# ProProject_AmaizeTrack.net
KiCad netlist of a schematic drawn in EasyEDA Pro
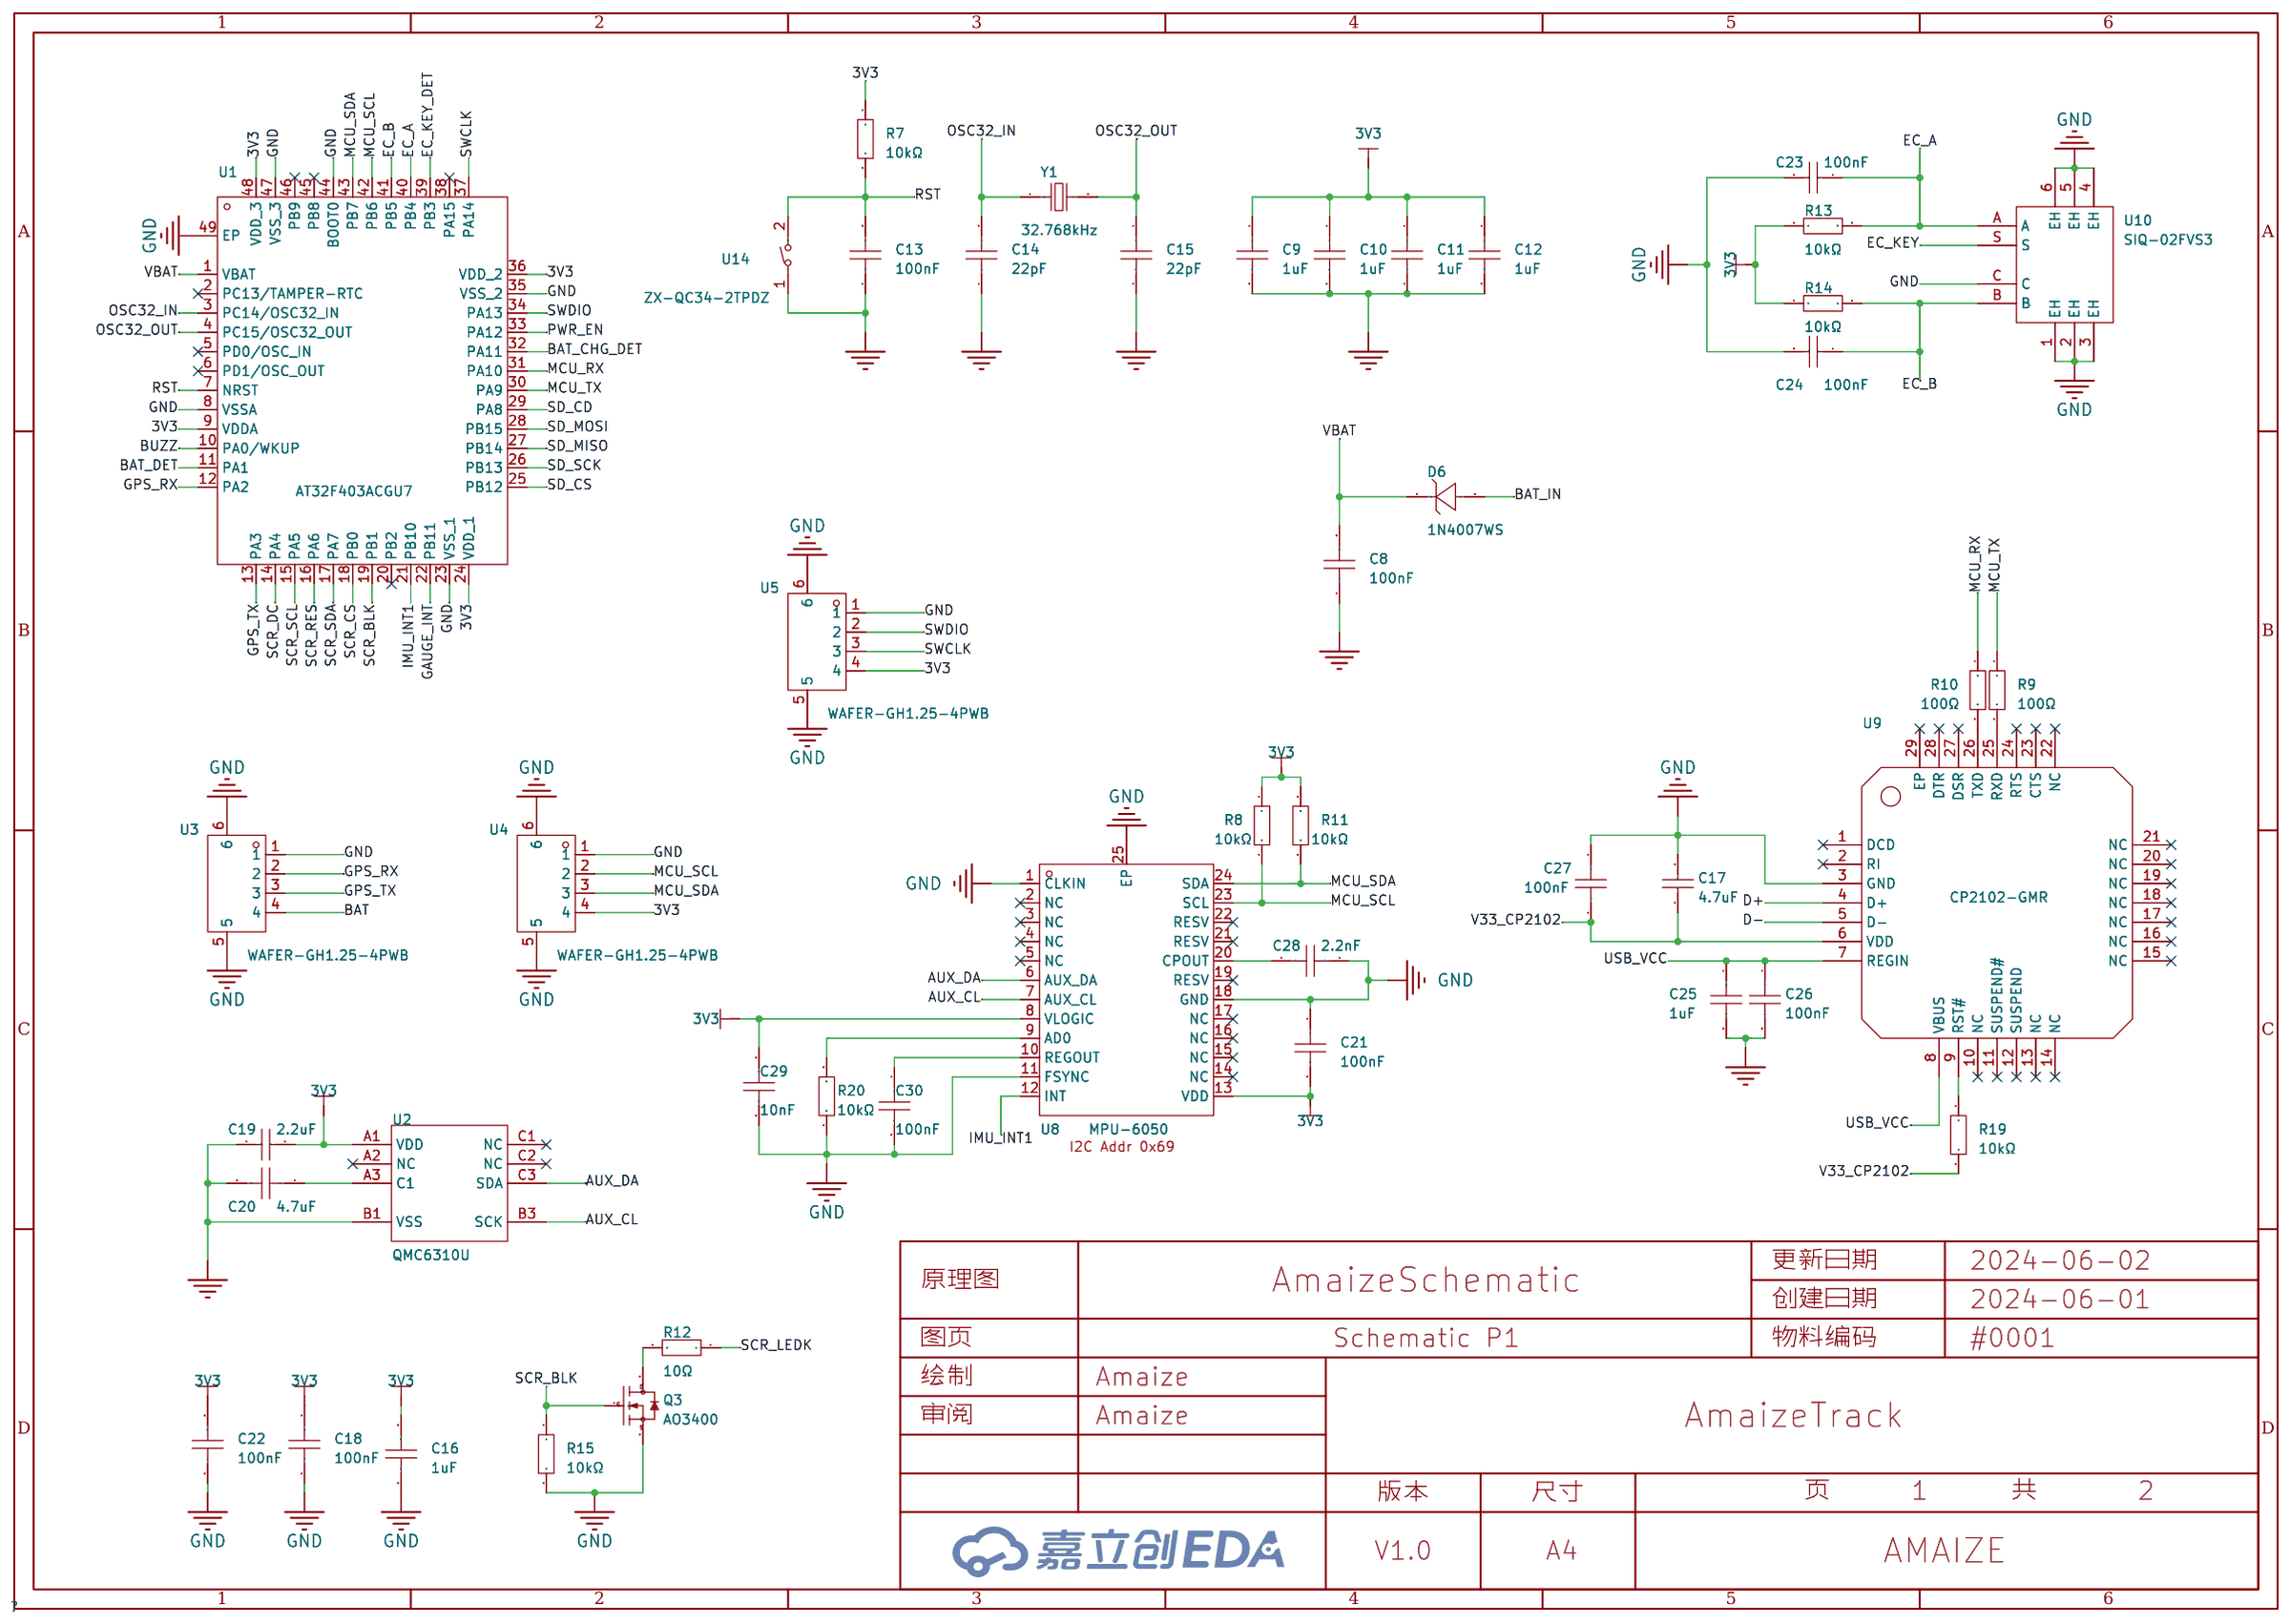
[diagram p0: Schematic P1]
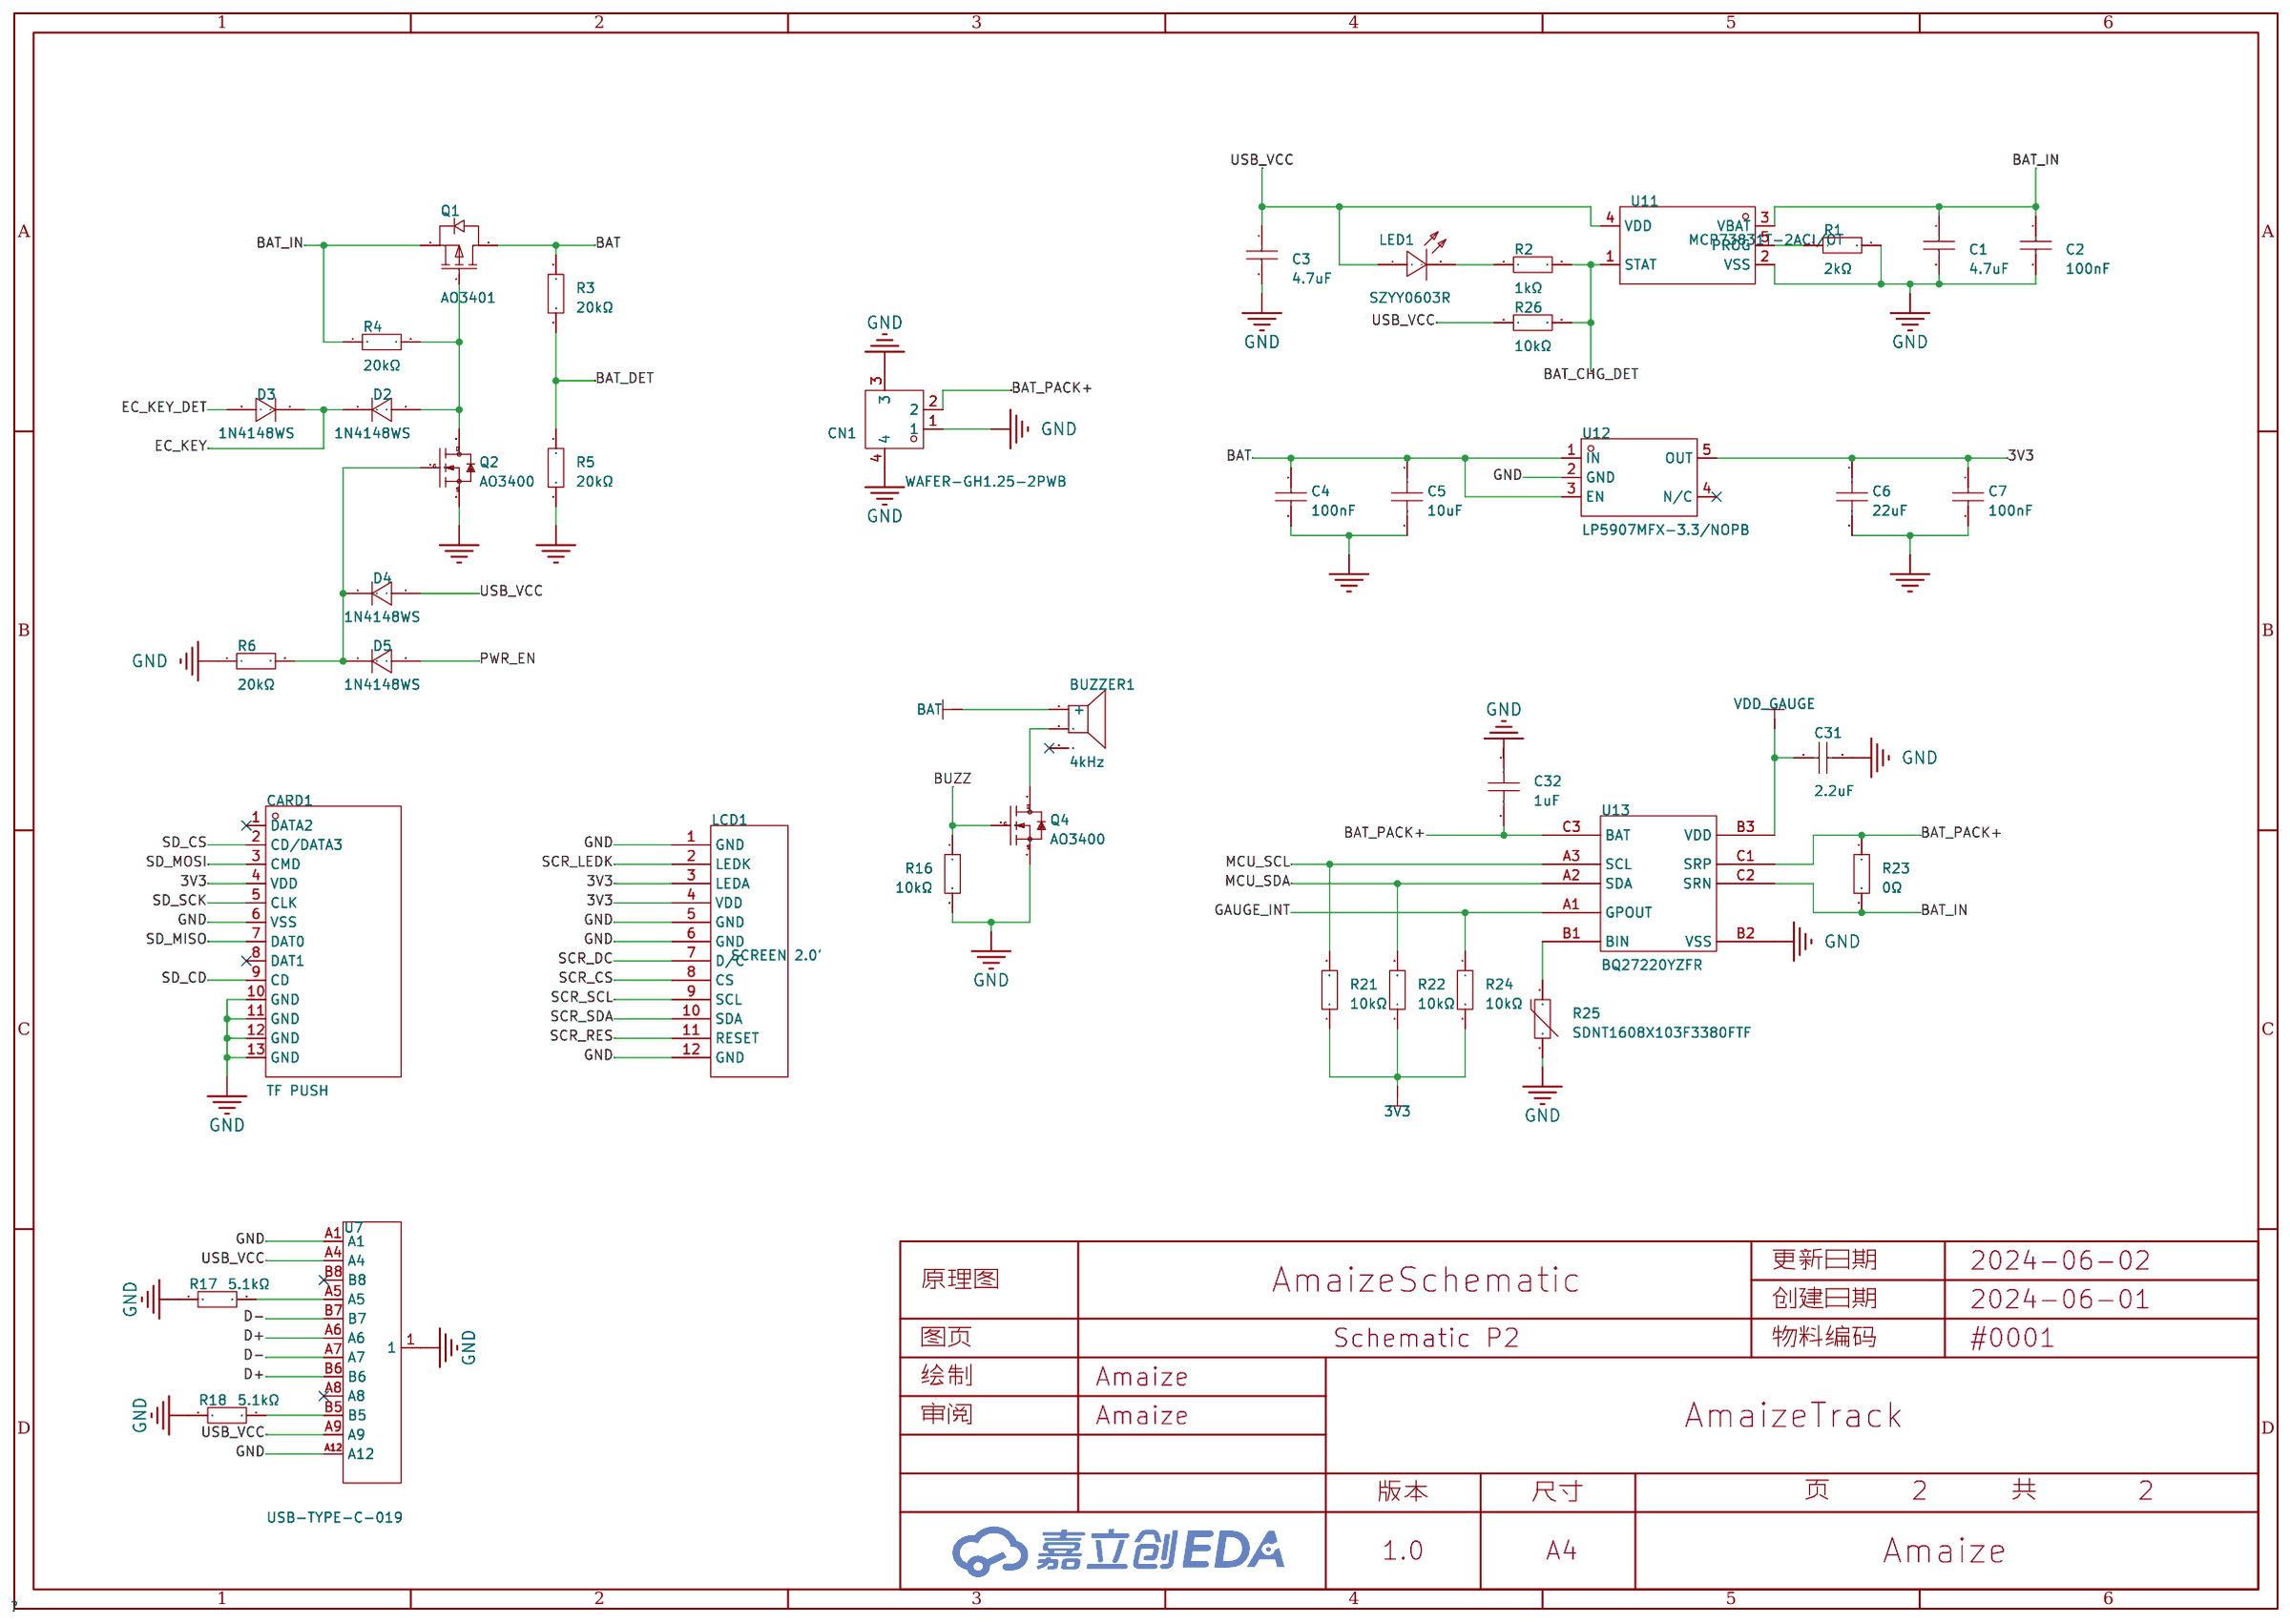
[diagram p1: Schematic P2]

(export (version "E")
  (design (tool "Eeschema 10.0.6"))
  (components
    (comp (ref "C8")
      (value "100nF")
      (footprint "easyedapro:C0603")
      (fields
        (field (name "Manufacturer Part") "CC0603KRX7R9BB104")
        (field (name "Manufacturer") "YAGEO(国巨)")
      )
      (libsource (lib "easyedapro") (part "CapAcitance"))
    )
    (comp (ref "C9")
      (value "1uF")
      (footprint "easyedapro:C0603")
      (fields
        (field (name "Manufacturer Part") "CL10A105KB8NNNC")
        (field (name "Manufacturer") "SAMSUNG(三星)")
      )
      (libsource (lib "easyedapro") (part "CapAcitance"))
    )
    (comp (ref "C10")
      (value "1uF")
      (footprint "easyedapro:C0603")
      (fields
        (field (name "Manufacturer Part") "CL10A105KB8NNNC")
        (field (name "Manufacturer") "SAMSUNG(三星)")
      )
      (libsource (lib "easyedapro") (part "CapAcitance"))
    )
    (comp (ref "C11")
      (value "1uF")
      (footprint "easyedapro:C0603")
      (fields
        (field (name "Manufacturer Part") "CL10A105KB8NNNC")
        (field (name "Manufacturer") "SAMSUNG(三星)")
      )
      (libsource (lib "easyedapro") (part "CapAcitance"))
    )
    (comp (ref "C12")
      (value "1uF")
      (footprint "easyedapro:C0603")
      (fields
        (field (name "Manufacturer Part") "CL10A105KB8NNNC")
        (field (name "Manufacturer") "SAMSUNG(三星)")
      )
      (libsource (lib "easyedapro") (part "CapAcitance"))
    )
    (comp (ref "C13")
      (value "100nF")
      (footprint "easyedapro:C0603")
      (fields
        (field (name "Manufacturer Part") "CC0603KRX7R9BB104")
        (field (name "Manufacturer") "YAGEO(国巨)")
      )
      (libsource (lib "easyedapro") (part "CapAcitance"))
    )
    (comp (ref "C14")
      (value "22pF")
      (footprint "easyedapro:C0603")
      (fields
        (field (name "Manufacturer Part") "CC0603JRNPO9BN220")
        (field (name "Manufacturer") "YAGEO(国巨)")
      )
      (libsource (lib "easyedapro") (part "CapAcitance"))
    )
    (comp (ref "C15")
      (value "22pF")
      (footprint "easyedapro:C0603")
      (fields
        (field (name "Manufacturer Part") "CC0603JRNPO9BN220")
        (field (name "Manufacturer") "YAGEO(国巨)")
      )
      (libsource (lib "easyedapro") (part "CapAcitance"))
    )
    (comp (ref "C16")
      (value "1uF")
      (footprint "easyedapro:C0603")
      (fields
        (field (name "Manufacturer Part") "CL10A105KB8NNNC")
        (field (name "Manufacturer") "SAMSUNG(三星)")
      )
      (libsource (lib "easyedapro") (part "CapAcitance"))
    )
    (comp (ref "C17")
      (value "4.7uF")
      (footprint "easyedapro:C0603")
      (description "容值:4.7uF;精度:±10%;额定电压:16V;材质(温度系数):X5R;")
      (fields
        (field (name "Manufacturer Part") "CL10A475KO8NNNC")
        (field (name "Manufacturer") "SAMSUNG(三星)")
      )
      (libsource (lib "easyedapro") (part "CL10A475KO8NNNC"))
    )
    (comp (ref "C18")
      (value "100nF")
      (footprint "easyedapro:C0603")
      (fields
        (field (name "Manufacturer Part") "CC0603KRX7R9BB104")
        (field (name "Manufacturer") "YAGEO(国巨)")
      )
      (libsource (lib "easyedapro") (part "CapAcitance"))
    )
    (comp (ref "C19")
      (value "2.2uF")
      (footprint "easyedapro:C0603")
      (description "容值:2.2uF;精度:±10%;额定电压:16V;材质(温度系数):X6S;")
      (fields
        (field (name "Manufacturer Part") "CL10A225KO8NNNC")
        (field (name "Manufacturer") "SAMSUNG(三星)")
      )
      (libsource (lib "easyedapro") (part "GRT188C81C225KE13D"))
    )
    (comp (ref "C20")
      (value "4.7uF")
      (footprint "easyedapro:C0603")
      (description "容值:4.7uF;精度:±10%;额定电压:16V;材质(温度系数):X6S;")
      (fields
        (field (name "Manufacturer Part") "CL10A475KO8NNNC")
        (field (name "Manufacturer") "SAMSUNG(三星)")
      )
      (libsource (lib "easyedapro") (part "GRT188C81C475KE13D"))
    )
    (comp (ref "C21")
      (value "100nF")
      (footprint "easyedapro:C0603")
      (description "容值:100nF;精度:±10%;额定电压:50V;材质(温度系数):X7R;")
      (fields
        (field (name "Manufacturer Part") "CC0603KRX7R9BB104")
        (field (name "Manufacturer") "YAGEO(国巨)")
      )
      (libsource (lib "easyedapro") (part "CC0603KRX7R9BB104"))
    )
    (comp (ref "C22")
      (value "100nF")
      (footprint "easyedapro:C0603")
      (fields
        (field (name "Manufacturer Part") "CC0603KRX7R9BB104")
        (field (name "Manufacturer") "YAGEO(国巨)")
      )
      (libsource (lib "easyedapro") (part "CapAcitance"))
    )
    (comp (ref "C23")
      (value "100nF")
      (footprint "easyedapro:C0805")
      (description "容值:100nF;精度:±10%;额定电压:50V;材质(温度系数):X7R;")
      (fields
        (field (name "Manufacturer Part") "CC0603KRX7R9BB104")
        (field (name "Manufacturer") "YAGEO(国巨)")
      )
      (libsource (lib "easyedapro") (part "CC0805KRX7R9BB104"))
    )
    (comp (ref "C24")
      (value "100nF")
      (footprint "easyedapro:C0805")
      (description "容值:100nF;精度:±10%;额定电压:50V;材质(温度系数):X7R;")
      (fields
        (field (name "Manufacturer Part") "CC0603KRX7R9BB104")
        (field (name "Manufacturer") "YAGEO(国巨)")
      )
      (libsource (lib "easyedapro") (part "CC0805KRX7R9BB104"))
    )
    (comp (ref "C25")
      (value "1uF")
      (footprint "easyedapro:C0603")
      (description "容值:1uF;精度:±10%;额定电压:50V;材质(温度系数):X5R;")
      (fields
        (field (name "Manufacturer Part") "CL10A105KB8NNNC")
        (field (name "Manufacturer") "SAMSUNG(三星)")
      )
      (libsource (lib "easyedapro") (part "CL10A105KB8NNNC"))
    )
    (comp (ref "C26")
      (value "100nF")
      (footprint "easyedapro:C0603")
      (description "容值:100nF;精度:±10%;额定电压:50V;材质(温度系数):X7R;")
      (fields
        (field (name "Manufacturer Part") "CC0603KRX7R9BB104")
        (field (name "Manufacturer") "YAGEO(国巨)")
      )
      (libsource (lib "easyedapro") (part "CC0603KRX7R9BB104"))
    )
    (comp (ref "C27")
      (value "100nF")
      (footprint "easyedapro:C0603")
      (description "容值:100nF;精度:±10%;额定电压:50V;材质(温度系数):X7R;")
      (fields
        (field (name "Manufacturer Part") "CC0603KRX7R9BB104")
        (field (name "Manufacturer") "YAGEO(国巨)")
      )
      (libsource (lib "easyedapro") (part "CC0603KRX7R9BB104"))
    )
    (comp (ref "C28")
      (value "2.2nF")
      (footprint "easyedapro:C0603")
      (fields
        (field (name "Manufacturer Part") "CC0603KRX7R9BB222")
        (field (name "Manufacturer") "YAGEO(国巨)")
      )
      (libsource (lib "easyedapro") (part "CapAcitance"))
    )
    (comp (ref "C29")
      (value "10nF")
      (footprint "easyedapro:C0603")
      (description "容值:1uF;精度:±10%;额定电压:50V;材质(温度系数):X5R;")
      (fields
        (field (name "Manufacturer Part") "CC0603KRX7R9BB103")
        (field (name "Manufacturer") "YAGEO(国巨)")
      )
      (libsource (lib "easyedapro") (part "CL10A105KB8NNNC"))
    )
    (comp (ref "C30")
      (value "100nF")
      (footprint "easyedapro:C0603")
      (description "容值:100nF;精度:±10%;额定电压:50V;材质(温度系数):X7R;")
      (fields
        (field (name "Manufacturer Part") "CC0603KRX7R9BB104")
        (field (name "Manufacturer") "YAGEO(国巨)")
      )
      (libsource (lib "easyedapro") (part "CC0603KRX7R9BB104"))
    )
    (comp (ref "D6")
      (value "1N4007WS")
      (footprint "easyedapro:SOD-123FL_L2.7-W1.8-LS3.8-RD")
      (description "二极管配置:独立式;正向压降(Vf):1.1V@1A;直流反向耐压(Vr):1kV;平均整流电流(Io):1A;")
      (fields (field (name "Manufacturer") "MDD"))
      (libsource (lib "easyedapro") (part "1N4007_C727082"))
    )
    (comp (ref "Q3")
      (value "AO3400")
      (footprint "easyedapro:SOT-23-3_L2.9-W1.3-P1.90-LS2.4-BR")
      (fields (field (name "Manufacturer") "Hottech(合科泰)"))
      (libsource (lib "easyedapro") (part "AO3400_C181090"))
    )
    (comp (ref "R7")
      (value "10kΩ")
      (footprint "easyedapro:R0603")
      (fields
        (field (name "Manufacturer Part") "0603WAF1002T5E")
        (field (name "Manufacturer") "UNI-ROYAL(厚声)")
      )
      (libsource (lib "easyedapro") (part "电阻"))
    )
    (comp (ref "R8")
      (value "10kΩ")
      (footprint "easyedapro:R0603")
      (fields
        (field (name "Manufacturer Part") "0603WAF1002T5E")
        (field (name "Manufacturer") "UNI-ROYAL(厚声)")
      )
      (libsource (lib "easyedapro") (part "电阻"))
    )
    (comp (ref "R9")
      (value "100Ω")
      (footprint "easyedapro:R0603")
      (fields
        (field (name "Manufacturer Part") "0603WAF1000T5E")
        (field (name "Manufacturer") "UNI-ROYAL(厚声)")
      )
      (libsource (lib "easyedapro") (part "电阻"))
    )
    (comp (ref "R10")
      (value "100Ω")
      (footprint "easyedapro:R0603")
      (fields
        (field (name "Manufacturer Part") "0603WAF1000T5E")
        (field (name "Manufacturer") "UNI-ROYAL(厚声)")
      )
      (libsource (lib "easyedapro") (part "电阻"))
    )
    (comp (ref "R11")
      (value "10kΩ")
      (footprint "easyedapro:R0603")
      (fields
        (field (name "Manufacturer Part") "0603WAF1002T5E")
        (field (name "Manufacturer") "UNI-ROYAL(厚声)")
      )
      (libsource (lib "easyedapro") (part "电阻"))
    )
    (comp (ref "R12")
      (value "10Ω")
      (footprint "easyedapro:R0603")
      (fields
        (field (name "Manufacturer Part") "0603WAF100JT5E")
        (field (name "Manufacturer") "UNI-ROYAL(厚声)")
      )
      (libsource (lib "easyedapro") (part "电阻"))
    )
    (comp (ref "R13")
      (value "10kΩ")
      (footprint "easyedapro:R0805")
      (description "电阻类型:厚膜电阻;阻值:10kΩ;精度:±1%;功率:125mW;最大工作电压:150V;温度系数:±100ppm/°C;")
      (fields
        (field (name "Manufacturer Part") "0603WAF1002T5E")
        (field (name "Manufacturer") "UNI-ROYAL(厚声)")
      )
      (libsource (lib "easyedapro") (part "0805W8F1002T5E"))
    )
    (comp (ref "R14")
      (value "10kΩ")
      (footprint "easyedapro:R0805")
      (description "电阻类型:厚膜电阻;阻值:10kΩ;精度:±1%;功率:125mW;最大工作电压:150V;温度系数:±100ppm/°C;")
      (fields
        (field (name "Manufacturer Part") "0603WAF1002T5E")
        (field (name "Manufacturer") "UNI-ROYAL(厚声)")
      )
      (libsource (lib "easyedapro") (part "0805W8F1002T5E"))
    )
    (comp (ref "R15")
      (value "10kΩ")
      (footprint "easyedapro:R0603")
      (fields
        (field (name "Manufacturer Part") "0603WAF1002T5E")
        (field (name "Manufacturer") "UNI-ROYAL(厚声)")
      )
      (libsource (lib "easyedapro") (part "电阻"))
    )
    (comp (ref "R19")
      (value "10kΩ")
      (footprint "easyedapro:R0603")
      (description "电阻类型:厚膜电阻;阻值:10kΩ;精度:±1%;功率:100mW;最大工作电压:75V;温度系数:±100ppm/°C;")
      (fields
        (field (name "Manufacturer Part") "0603WAF1002T5E")
        (field (name "Manufacturer") "UNI-ROYAL(厚声)")
      )
      (libsource (lib "easyedapro") (part "0603WAF1002T5E"))
    )
    (comp (ref "R20")
      (value "10kΩ")
      (footprint "easyedapro:R0603")
      (description "电阻类型:厚膜电阻;阻值:10kΩ;精度:±1%;功率:100mW;最大工作电压:75V;温度系数:±100ppm/°C;")
      (fields
        (field (name "Manufacturer Part") "0603WAF1002T5E")
        (field (name "Manufacturer") "UNI-ROYAL(厚声)")
      )
      (libsource (lib "easyedapro") (part "0603WAF1002T5E"))
    )
    (comp (ref "U1")
      (value "AT32F403ACGU7")
      (footprint "easyedapro:QFN-48_L6.0-W6.0-P0.40-BL-EP4.2")
      (fields (field (name "Manufacturer") "ARTERY(雅特力)"))
      (libsource (lib "easyedapro") (part "AT32F403ACGU7"))
    )
    (comp (ref "U2")
      (value "QMC6310U")
      (footprint "easyedapro:LGA-8_L1.2-W1.2-P0.40-R3-C3-TL")
      (description "地磁传感器M-sensor，2.5~3.3V, 16 Bit ADC,量程±30 Gauss，I2C")
      (fields (field (name "Manufacturer") "QST(上海矽睿)"))
      (libsource (lib "easyedapro") (part "QMC6310"))
    )
    (comp (ref "U3")
      (value "WAFER-GH1.25-4PWB")
      (footprint "easyedapro:CONN-SMD_4P-P1.25_XUNPU_WAFER-GH1.25-4PWB")
      (description "插针结构:1x4P;间距:1.25mm;安装方式:卧贴;参考系列:GH;总PIN数:4P;排数:1;每排PIN数:4;额定电流:1A;工作温度范围:-25°C~+85°C;")
      (fields (field (name "Manufacturer") "XUNPU(讯普)"))
      (libsource (lib "easyedapro") (part "WAFER-GH1.25-4PWB"))
    )
    (comp (ref "U4")
      (value "WAFER-GH1.25-4PWB")
      (footprint "easyedapro:CONN-SMD_4P-P1.25_XUNPU_WAFER-GH1.25-4PWB")
      (description "插针结构:1x4P;间距:1.25mm;安装方式:卧贴;参考系列:GH;总PIN数:4P;排数:1;每排PIN数:4;额定电流:1A;工作温度范围:-25°C~+85°C;")
      (fields (field (name "Manufacturer") "XUNPU(讯普)"))
      (libsource (lib "easyedapro") (part "WAFER-GH1.25-4PWB"))
    )
    (comp (ref "U5")
      (value "WAFER-GH1.25-4PWB")
      (footprint "easyedapro:CONN-SMD_4P-P1.25_XUNPU_WAFER-GH1.25-4PWB")
      (description "插针结构:1x4P;间距:1.25mm;安装方式:卧贴;参考系列:GH;总PIN数:4P;排数:1;每排PIN数:4;额定电流:1A;工作温度范围:-25°C~+85°C;")
      (fields (field (name "Manufacturer") "XUNPU(讯普)"))
      (libsource (lib "easyedapro") (part "WAFER-GH1.25-4PWB"))
    )
    (comp (ref "U8")
      (value "MPU-6050")
      (footprint "easyedapro:QFN-24_L4.0-W4.0-P0.50-BL-EP2.7")
      (description "传感器类型:加速度计陀螺仪;")
      (fields (field (name "Manufacturer") "TDK InvenSense(应美盛)"))
      (libsource (lib "easyedapro") (part "MPU-6050_C24112"))
    )
    (comp (ref "U9")
      (value "CP2102-GMR")
      (footprint "easyedapro:WQFN-28_L5.0-W5.0-P0.50-BL-EP3.2")
      (description "应用功能:收发器;接口协议:USB;数据速率:1Mbps;")
      (fields (field (name "Manufacturer") "SKYWORKS/SILICON LABS(芯科)"))
      (libsource (lib "easyedapro") (part "CP2102-GMR"))
    )
    (comp (ref "U10")
      (value "SIQ-02FVS3")
      (footprint "easyedapro:SW-SMD_SIQ-02FVS3_1")
      (fields (field (name "Manufacturer") "MITSUMI(美上美)"))
      (libsource (lib "easyedapro") (part "SIQ-02FVS3"))
    )
    (comp (ref "U14")
      (value "ZX-QC34-2TPDZ")
      (footprint "easyedapro:KEY-SMD_L3.9-W3.0-LS5.0-EH")
      (fields (field (name "Manufacturer") "Megastar(兆星)"))
      (libsource (lib "easyedapro") (part "ZX-QC34-2TPDZ"))
    )
    (comp (ref "Y1")
      (value "32.768kHz")
      (footprint "easyedapro:FC-135R_L3.2-W1.5")
      (description "晶振类型:贴片晶振;频率:32.768kHz;常温频差:±20ppm;外接负载电容:12.5pF;")
      (fields (field (name "Manufacturer Part") "Q13FC13500004") (field (name "Manufacturer") "EPSON(爱普生)"))
      (libsource (lib "easyedapro") (part "Q13FC1350000400"))
    )
    (comp (ref "BUZZER1")
      (value "4kHz")
      (footprint "easyedapro:BUZ-SMD_FST-5030")
      (description "驱动方式:无源(外部驱动);构造类型:电磁式;频率:4kHz;声压(SPL):80dB@3V,10cm;")
      (fields (field (name "Manufacturer Part") "FUET-5030") (field (name "Manufacturer") "FUET(福声科技)"))
      (libsource (lib "easyedapro") (part "FST-5030"))
    )
    (comp (ref "C1")
      (value "4.7uF")
      (footprint "easyedapro:C0805")
      (description "容值:4.7uF;精度:±10%;额定电压:50V;材质(温度系数):X5R;")
      (fields
        (field (name "Manufacturer Part") "CL21A475KBQNNNE")
        (field (name "Manufacturer") "SAMSUNG(三星)")
      )
      (libsource (lib "easyedapro") (part "CL21A475KBQNNNE"))
    )
    (comp (ref "C2")
      (value "100nF")
      (footprint "easyedapro:C0805")
      (description "容值:100nF;精度:±10%;额定电压:50V;材质(温度系数):X7R;")
      (fields
        (field (name "Manufacturer Part") "CC0603KRX7R9BB104")
        (field (name "Manufacturer") "YAGEO(国巨)")
      )
      (libsource (lib "easyedapro") (part "CC0805KRX7R9BB104"))
    )
    (comp (ref "C3")
      (value "4.7uF")
      (footprint "easyedapro:C0805")
      (description "容值:4.7uF;精度:±10%;额定电压:50V;材质(温度系数):X5R;")
      (fields
        (field (name "Manufacturer Part") "CL21A475KBQNNNE")
        (field (name "Manufacturer") "SAMSUNG(三星)")
      )
      (libsource (lib "easyedapro") (part "CL21A475KBQNNNE"))
    )
    (comp (ref "C4")
      (value "100nF")
      (footprint "easyedapro:C0805")
      (description "容值:100nF;精度:±10%;额定电压:50V;材质(温度系数):X7R;")
      (fields
        (field (name "Manufacturer Part") "CC0603KRX7R9BB104")
        (field (name "Manufacturer") "YAGEO(国巨)")
      )
      (libsource (lib "easyedapro") (part "CC0805KRX7R9BB104"))
    )
    (comp (ref "C5")
      (value "10uF")
      (footprint "easyedapro:C0805")
      (description "容值:10uF;精度:±10%;额定电压:50V;材质(温度系数):X5R;")
      (fields
        (field (name "Manufacturer Part") "GRM188R61E106KA73D")
        (field (name "Manufacturer") "muRata(村田)")
      )
      (libsource (lib "easyedapro") (part "GRM21BR61H106KE43L"))
    )
    (comp (ref "C6")
      (value "22uF")
      (footprint "easyedapro:C0805")
      (description "容值:22uF;精度:±20%;额定电压:25V;材质(温度系数):X5R;")
      (fields
        (field (name "Manufacturer Part") "CL31A226KAHNNNE")
        (field (name "Manufacturer") "SAMSUNG(三星)")
      )
      (libsource (lib "easyedapro") (part "CL21A226MAQNNNE"))
    )
    (comp (ref "C7")
      (value "100nF")
      (footprint "easyedapro:C0805")
      (description "容值:100nF;精度:±10%;额定电压:50V;材质(温度系数):X7R;")
      (fields
        (field (name "Manufacturer Part") "CC0603KRX7R9BB104")
        (field (name "Manufacturer") "YAGEO(国巨)")
      )
      (libsource (lib "easyedapro") (part "CC0805KRX7R9BB104"))
    )
    (comp (ref "C31")
      (value "2.2uF")
      (footprint "easyedapro:C0603")
      (description "容值:2.2uF;精度:±10%;额定电压:16V;材质(温度系数):X5R;")
      (fields
        (field (name "Manufacturer Part") "CL10A225KO8NNNC")
        (field (name "Manufacturer") "SAMSUNG(三星)")
      )
      (libsource (lib "easyedapro") (part "CL10A225KO8NNNC"))
    )
    (comp (ref "C32")
      (value "1uF")
      (footprint "easyedapro:C0603")
      (description "容值:1uF;精度:±10%;额定电压:50V;材质(温度系数):X5R;")
      (fields
        (field (name "Manufacturer Part") "CL10A105KB8NNNC")
        (field (name "Manufacturer") "SAMSUNG(三星)")
      )
      (libsource (lib "easyedapro") (part "CL10A105KB8NNNC"))
    )
    (comp (ref "CARD1")
      (value "TF PUSH")
      (footprint "easyedapro:TF-SMD_TF-115-BCP9")
      (fields (field (name "Manufacturer") "SHOU HAN(首韩)"))
      (libsource (lib "easyedapro") (part "TF-115-BCP9"))
    )
    (comp (ref "CN1")
      (value "WAFER-GH1.25-2PWB")
      (footprint "easyedapro:CONN-TH_2P-P1.25_XUNPU_WAFER-GH1.25-2PWB")
      (description "插针结构:1x2P;间距:1.25mm;安装方式:卧贴;参考系列:GH;总PIN数:2P;排数:1;每排PIN数:2;额定电流:1A;工作温度范围:-25°C~+85°C;")
      (fields (field (name "Manufacturer") "XUNPU(讯普)"))
      (libsource (lib "easyedapro") (part "WAFER-GH1.25-2PWB"))
    )
    (comp (ref "D2")
      (value "1N4148WS")
      (footprint "easyedapro:SOD-323_L1.8-W1.3-LS2.5-RD")
      (description "二极管配置:独立式;正向压降(Vf):1.25V@150mA;直流反向耐压(Vr):100V;平均整流电流(Io):150mA;功率:200mW;反向恢复时间(trr):4ns;")
      (fields (field (name "Manufacturer") "CJ(江苏长电/长晶)"))
      (libsource (lib "easyedapro") (part "1N4148WS T4"))
    )
    (comp (ref "D3")
      (value "1N4148WS")
      (footprint "easyedapro:SOD-323_L1.8-W1.3-LS2.5-RD")
      (description "二极管配置:独立式;正向压降(Vf):1.25V@150mA;直流反向耐压(Vr):100V;平均整流电流(Io):150mA;功率:200mW;反向恢复时间(trr):4ns;")
      (fields (field (name "Manufacturer") "CJ(江苏长电/长晶)"))
      (libsource (lib "easyedapro") (part "1N4148WS T4"))
    )
    (comp (ref "D4")
      (value "1N4148WS")
      (footprint "easyedapro:SOD-323_L1.8-W1.3-LS2.5-RD")
      (description "二极管配置:独立式;正向压降(Vf):1.25V@150mA;直流反向耐压(Vr):100V;平均整流电流(Io):150mA;功率:200mW;反向恢复时间(trr):4ns;")
      (fields (field (name "Manufacturer") "CJ(江苏长电/长晶)"))
      (libsource (lib "easyedapro") (part "1N4148WS T4"))
    )
    (comp (ref "D5")
      (value "1N4148WS")
      (footprint "easyedapro:SOD-323_L1.8-W1.3-LS2.5-RD")
      (description "二极管配置:独立式;正向压降(Vf):1.25V@150mA;直流反向耐压(Vr):100V;平均整流电流(Io):150mA;功率:200mW;反向恢复时间(trr):4ns;")
      (fields (field (name "Manufacturer") "CJ(江苏长电/长晶)"))
      (libsource (lib "easyedapro") (part "1N4148WS T4"))
    )
    (comp (ref "LCD1")
      (value "SCREEN 2.0'")
      (footprint "easyedapro:2.0-TFT-IPS")
      (description "2.0寸TFT IPS液晶显示屏 12PIN(焊接) 240x320 ST7789 SPI")
      (libsource (lib "easyedapro") (part "2.0-TFT-IPS"))
    )
    (comp (ref "LED1")
      (value "SZYY0603R")
      (footprint "easyedapro:LED0603-R-RD")
      (fields (field (name "Manufacturer") "yongyu(永裕光电)"))
      (libsource (lib "easyedapro") (part "SZYY0603R"))
    )
    (comp (ref "Q1")
      (value "AO3401")
      (footprint "easyedapro:SOT-23-3_L2.9-W1.4-P1.90-LS2.6-BR")
      (fields (field (name "Manufacturer") "TWGMC(台湾迪嘉)"))
      (libsource (lib "easyedapro") (part "AO3401_C727156"))
    )
    (comp (ref "Q2")
      (value "AO3400")
      (footprint "easyedapro:SOT-23-3_L2.9-W1.3-P1.90-LS2.4-BR")
      (fields (field (name "Manufacturer") "Hottech(合科泰)"))
      (libsource (lib "easyedapro") (part "AO3400_C181090"))
    )
    (comp (ref "Q4")
      (value "AO3400")
      (footprint "easyedapro:SOT-23-3_L2.9-W1.3-P1.90-LS2.4-BR")
      (fields (field (name "Manufacturer") "Hottech(合科泰)"))
      (libsource (lib "easyedapro") (part "AO3400_C181090"))
    )
    (comp (ref "R1")
      (value "2kΩ")
      (footprint "easyedapro:R0603")
      (fields
        (field (name "Manufacturer Part") "0603WAF2001T5E")
        (field (name "Manufacturer") "UNI-ROYAL(厚声)")
      )
      (libsource (lib "easyedapro") (part "电阻"))
    )
    (comp (ref "R2")
      (value "1kΩ")
      (footprint "easyedapro:R0603")
      (fields
        (field (name "Manufacturer Part") "0603WAF1001T5E")
        (field (name "Manufacturer") "UNI-ROYAL(厚声)")
      )
      (libsource (lib "easyedapro") (part "电阻"))
    )
    (comp (ref "R3")
      (value "20kΩ")
      (footprint "easyedapro:R0603")
      (fields
        (field (name "Manufacturer Part") "0603WAF2002T5E")
        (field (name "Manufacturer") "UNI-ROYAL(厚声)")
      )
      (libsource (lib "easyedapro") (part "电阻"))
    )
    (comp (ref "R4")
      (value "20kΩ")
      (footprint "easyedapro:R0603")
      (fields
        (field (name "Manufacturer Part") "0603WAF2002T5E")
        (field (name "Manufacturer") "UNI-ROYAL(厚声)")
      )
      (libsource (lib "easyedapro") (part "电阻"))
    )
    (comp (ref "R5")
      (value "20kΩ")
      (footprint "easyedapro:R0603")
      (fields
        (field (name "Manufacturer Part") "0603WAF2002T5E")
        (field (name "Manufacturer") "UNI-ROYAL(厚声)")
      )
      (libsource (lib "easyedapro") (part "电阻"))
    )
    (comp (ref "R6")
      (value "20kΩ")
      (footprint "easyedapro:R0603")
      (fields
        (field (name "Manufacturer Part") "0603WAF2002T5E")
        (field (name "Manufacturer") "UNI-ROYAL(厚声)")
      )
      (libsource (lib "easyedapro") (part "电阻"))
    )
    (comp (ref "R16")
      (value "10kΩ")
      (footprint "easyedapro:R0805")
      (description "电阻类型:厚膜电阻;阻值:10kΩ;精度:±1%;功率:125mW;最大工作电压:150V;温度系数:±100ppm/°C;")
      (fields
        (field (name "Manufacturer Part") "0603WAF1002T5E")
        (field (name "Manufacturer") "UNI-ROYAL(厚声)")
      )
      (libsource (lib "easyedapro") (part "0805W8F1002T5E"))
    )
    (comp (ref "R17")
      (value "5.1kΩ")
      (footprint "easyedapro:R0603")
      (fields
        (field (name "Manufacturer Part") "0603WAF5101T5E")
        (field (name "Manufacturer") "UNI-ROYAL(厚声)")
      )
      (libsource (lib "easyedapro") (part "电阻"))
    )
    (comp (ref "R18")
      (value "5.1kΩ")
      (footprint "easyedapro:R0603")
      (fields
        (field (name "Manufacturer Part") "0603WAF5101T5E")
        (field (name "Manufacturer") "UNI-ROYAL(厚声)")
      )
      (libsource (lib "easyedapro") (part "电阻"))
    )
    (comp (ref "R21")
      (value "10kΩ")
      (footprint "easyedapro:R0603")
      (description "电阻类型:厚膜电阻;阻值:10kΩ;精度:±1%;功率:100mW;最大工作电压:75V;温度系数:±100ppm/°C;")
      (fields
        (field (name "Manufacturer Part") "0603WAF1002T5E")
        (field (name "Manufacturer") "UNI-ROYAL(厚声)")
      )
      (libsource (lib "easyedapro") (part "0603WAF1002T5E"))
    )
    (comp (ref "R22")
      (value "10kΩ")
      (footprint "easyedapro:R0603")
      (description "电阻类型:厚膜电阻;阻值:10kΩ;精度:±1%;功率:100mW;最大工作电压:75V;温度系数:±100ppm/°C;")
      (fields
        (field (name "Manufacturer Part") "0603WAF1002T5E")
        (field (name "Manufacturer") "UNI-ROYAL(厚声)")
      )
      (libsource (lib "easyedapro") (part "0603WAF1002T5E"))
    )
    (comp (ref "R23")
      (value "0Ω")
      (footprint "easyedapro:R0402")
      (description "电阻类型:厚膜电阻;阻值:49.9Ω;精度:±1%;功率:62.5mW;最大工作电压:50V;温度系数:±100ppm/°C;")
      (fields
        (field (name "Manufacturer Part") "25121WF0000T4E")
        (field (name "Manufacturer") "UNI-ROYAL(厚声)")
      )
      (libsource (lib "easyedapro") (part "0402WGF499JTCE"))
    )
    (comp (ref "R24")
      (value "10kΩ")
      (footprint "easyedapro:R0603")
      (description "电阻类型:厚膜电阻;阻值:10kΩ;精度:±1%;功率:100mW;最大工作电压:75V;温度系数:±100ppm/°C;")
      (fields
        (field (name "Manufacturer Part") "0603WAF1002T5E")
        (field (name "Manufacturer") "UNI-ROYAL(厚声)")
      )
      (libsource (lib "easyedapro") (part "0603WAF1002T5E"))
    )
    (comp (ref "R25")
      (value "SDNT1608X103F3380FTF")
      (footprint "easyedapro:R0805")
      (description "阻值(25°C):10kΩ;B值(25°C/50°C):3950K;电阻精度:±1%;功率:200mW;B值精度:±1%;最大稳态电流(25°C):440uA;")
      (fields (field (name "Manufacturer") "Sunlord(顺络)"))
      (libsource (lib "easyedapro") (part "SDNT2012X103F3950FTF"))
    )
    (comp (ref "R26")
      (value "10kΩ")
      (footprint "easyedapro:R0603")
      (description "电阻类型:厚膜电阻;阻值:10kΩ;精度:±1%;功率:100mW;最大工作电压:75V;温度系数:±100ppm/°C;")
      (fields
        (field (name "Manufacturer Part") "0603WAF1002T5E")
        (field (name "Manufacturer") "UNI-ROYAL(厚声)")
      )
      (libsource (lib "easyedapro") (part "0603WAF1002T5E"))
    )
    (comp (ref "U7")
      (value "USB-TYPE-C-019")
      (footprint "easyedapro:TYPE-C-SMD_HX-TYPE-C-16PIN")
      (description "连接器类型:Type-C;标准:-;公母:母;端口数量:1;触点数量:16P;安装方式:卧贴;额定电流 - 电源:3A;工作温度范围:-25°C~+85°C;")
      (fields (field (name "Manufacturer") "DEALON(德艺隆)"))
      (libsource (lib "easyedapro") (part "USB-TYPE-C-019"))
    )
    (comp (ref "U11")
      (value "MCP73831T-2ACI/OT")
      (footprint "easyedapro:SOT-23-5_L3.0-W1.7-P0.95-LS2.8-BL")
      (description "电源电压:6V;最大充电电流:500mA;电池类型:锂离子/聚合物;电池节数:1;")
      (fields (field (name "Manufacturer") "MICROCHIP(美国微芯)"))
      (libsource (lib "easyedapro") (part "MCP73831T-2ACI/OT"))
    )
    (comp (ref "U12")
      (value "LP5907MFX-3.3/NOPB")
      (footprint "easyedapro:SOT-23-5_L3.0-W1.7-P0.95-LS2.8-BR")
      (description "输出类型:固定;最大输入电压:5.5V;输出电压:3.3V;最大输出电流:250mA;电源纹波抑制比(PSRR):90dB;输出极性:正极;")
      (fields (field (name "Manufacturer") "TI(德州仪器)"))
      (libsource (lib "easyedapro") (part "LP5907MFX-3.3/NOPB"))
    )
    (comp (ref "U13")
      (value "BQ27220YZFR")
      (footprint "easyedapro:BQ27220")
      (fields (field (name "Manufacturer") "TI(德州仪器)"))
      (libsource (lib "easyedapro") (part "BQ27220"))
    )
  )
  (nets
    (net (code "1") (name "3V3") (class "Default")
      (node (ref "C10") (pin "1") (pinfunction "1_1") (pintype "input"))
      (node (ref "C11") (pin "1") (pinfunction "1_1") (pintype "input"))
      (node (ref "C12") (pin "1") (pinfunction "1_1") (pintype "input"))
      (node (ref "C16") (pin "2") (pinfunction "2_2") (pintype "input"))
      (node (ref "C18") (pin "2") (pinfunction "2_2") (pintype "input"))
      (node (ref "C19") (pin "2") (pinfunction "2_2") (pintype "input"))
      (node (ref "C21") (pin "2") (pinfunction "2_2") (pintype "unspecified"))
      (node (ref "C22") (pin "2") (pinfunction "2_2") (pintype "input"))
      (node (ref "C29") (pin "2") (pinfunction "2_2") (pintype "unspecified"))
      (node (ref "C6") (pin "1") (pinfunction "1_1") (pintype "unspecified"))
      (node (ref "C7") (pin "1") (pinfunction "1_1") (pintype "input"))
      (node (ref "C9") (pin "1") (pinfunction "1_1") (pintype "input"))
      (node (ref "CARD1") (pin "4") (pinfunction "VDD_4") (pintype "unspecified"))
      (node (ref "LCD1") (pin "3") (pinfunction "LEDA_3") (pintype "input"))
      (node (ref "LCD1") (pin "4") (pinfunction "VDD_4") (pintype "input"))
      (node (ref "R11") (pin "1") (pinfunction "1_1") (pintype "input"))
      (node (ref "R13") (pin "1") (pinfunction "1_1") (pintype "input"))
      (node (ref "R14") (pin "1") (pinfunction "1_1") (pintype "input"))
      (node (ref "R21") (pin "1") (pinfunction "1_1") (pintype "input"))
      (node (ref "R22") (pin "1") (pinfunction "1_1") (pintype "input"))
      (node (ref "R24") (pin "2") (pinfunction "2_2") (pintype "input"))
      (node (ref "R7") (pin "1") (pinfunction "1_1") (pintype "input"))
      (node (ref "R8") (pin "1") (pinfunction "1_1") (pintype "input"))
      (node (ref "U1") (pin "24") (pinfunction "VDD_1_24") (pintype "input"))
      (node (ref "U1") (pin "36") (pinfunction "VDD_2_36") (pintype "input"))
      (node (ref "U1") (pin "48") (pinfunction "VDD_3_48") (pintype "input"))
      (node (ref "U1") (pin "9") (pinfunction "VDDA_9") (pintype "input"))
      (node (ref "U12") (pin "5") (pinfunction "OUT_5") (pintype "unspecified"))
      (node (ref "U2") (pin "A1") (pinfunction "VDD_A1") (pintype "unspecified"))
      (node (ref "U4") (pin "4") (pinfunction "4_4") (pintype "unspecified"))
      (node (ref "U5") (pin "4") (pinfunction "4_4") (pintype "unspecified"))
      (node (ref "U8") (pin "13") (pinfunction "VDD_13") (pintype "unspecified"))
      (node (ref "U8") (pin "8") (pinfunction "VLOGIC_8") (pintype "unspecified"))
    )
    (net (code "2") (name "AUX_CL") (class "Default")
      (node (ref "U2") (pin "B3") (pinfunction "SCK_B3") (pintype "unspecified"))
      (node (ref "U8") (pin "7") (pinfunction "AUX_CL_7") (pintype "unspecified"))
    )
    (net (code "3") (name "AUX_DA") (class "Default")
      (node (ref "U2") (pin "C3") (pinfunction "SDA_C3") (pintype "unspecified"))
      (node (ref "U8") (pin "6") (pinfunction "AUX_DA_6") (pintype "unspecified"))
    )
    (net (code "4") (name "BAT") (class "Default")
      (node (ref "BUZZER1") (pin "1") (pinfunction "+_1") (pintype "input"))
      (node (ref "C4") (pin "1") (pinfunction "1_1") (pintype "input"))
      (node (ref "C5") (pin "1") (pinfunction "1_1") (pintype "unspecified"))
      (node (ref "Q1") (pin "3") (pinfunction "D_3") (pintype "unspecified"))
      (node (ref "R3") (pin "1") (pinfunction "1_1") (pintype "input"))
      (node (ref "U12") (pin "1") (pinfunction "IN_1") (pintype "unspecified"))
      (node (ref "U12") (pin "3") (pinfunction "EN_3") (pintype "unspecified"))
      (node (ref "U3") (pin "4") (pinfunction "4_4") (pintype "unspecified"))
    )
    (net (code "5") (name "BAT_CHG_DET") (class "Default")
      (node (ref "R2") (pin "2") (pinfunction "2_2") (pintype "input"))
      (node (ref "R26") (pin "2") (pinfunction "2_2") (pintype "input"))
      (node (ref "U1") (pin "32") (pinfunction "PA11_32") (pintype "input"))
      (node (ref "U11") (pin "1") (pinfunction "STAT_1") (pintype "input"))
    )
    (net (code "6") (name "BAT_DET") (class "Default")
      (node (ref "R3") (pin "2") (pinfunction "2_2") (pintype "input"))
      (node (ref "R5") (pin "1") (pinfunction "1_1") (pintype "input"))
      (node (ref "U1") (pin "11") (pinfunction "PA1_11") (pintype "input"))
    )
    (net (code "7") (name "BAT_IN") (class "Default")
      (node (ref "C1") (pin "1") (pinfunction "1_1") (pintype "input"))
      (node (ref "C2") (pin "1") (pinfunction "1_1") (pintype "input"))
      (node (ref "D6") (pin "2") (pinfunction "A_2") (pintype "unspecified"))
      (node (ref "Q1") (pin "2") (pinfunction "S_2") (pintype "unspecified"))
      (node (ref "R23") (pin "2") (pinfunction "2_2") (pintype "input"))
      (node (ref "R4") (pin "1") (pinfunction "1_1") (pintype "input"))
      (node (ref "U11") (pin "3") (pinfunction "VBAT_3") (pintype "input"))
      (node (ref "U13") (pin "C2") (pinfunction "SRN_C2") (pintype "unspecified"))
    )
    (net (code "8") (name "BAT_PACK+") (class "Default")
      (node (ref "C32") (pin "2") (pinfunction "2_2") (pintype "unspecified"))
      (node (ref "CN1") (pin "2") (pinfunction "2_2") (pintype "unspecified"))
      (node (ref "R23") (pin "1") (pinfunction "1_1") (pintype "input"))
      (node (ref "U13") (pin "C1") (pinfunction "SRP_C1") (pintype "unspecified"))
      (node (ref "U13") (pin "C3") (pinfunction "BAT_C3") (pintype "unspecified"))
    )
    (net (code "9") (name "BUZZ") (class "Default")
      (node (ref "Q4") (pin "1") (pinfunction "G_1") (pintype "unspecified"))
      (node (ref "R16") (pin "1") (pinfunction "1_1") (pintype "input"))
      (node (ref "U1") (pin "10") (pinfunction "PA0/WKUP_10") (pintype "input"))
    )
    (net (code "10") (name "D+") (class "Default")
      (node (ref "U7") (pin "A6") (pinfunction "A6_A6") (pintype "unspecified"))
      (node (ref "U7") (pin "B6") (pinfunction "B6_B6") (pintype "unspecified"))
      (node (ref "U9") (pin "4") (pinfunction "D+_4") (pintype "unspecified"))
    )
    (net (code "11") (name "D-") (class "Default")
      (node (ref "U7") (pin "A7") (pinfunction "A7_A7") (pintype "unspecified"))
      (node (ref "U7") (pin "B7") (pinfunction "B7_B7") (pintype "unspecified"))
      (node (ref "U9") (pin "5") (pinfunction "D-_5") (pintype "unspecified"))
    )
    (net (code "12") (name "EC_A") (class "Default")
      (node (ref "C23") (pin "1") (pinfunction "1_1") (pintype "input"))
      (node (ref "R13") (pin "2") (pinfunction "2_2") (pintype "input"))
      (node (ref "U1") (pin "40") (pinfunction "PB4_40") (pintype "input"))
      (node (ref "U10") (pin "A") (pinfunction "A_A") (pintype "unspecified"))
    )
    (net (code "13") (name "EC_B") (class "Default")
      (node (ref "C24") (pin "1") (pinfunction "1_1") (pintype "input"))
      (node (ref "R14") (pin "2") (pinfunction "2_2") (pintype "input"))
      (node (ref "U1") (pin "41") (pinfunction "PB5_41") (pintype "input"))
      (node (ref "U10") (pin "B") (pinfunction "B_B") (pintype "unspecified"))
    )
    (net (code "14") (name "EC_KEY") (class "Default")
      (node (ref "D2") (pin "1") (pinfunction "K_1") (pintype "unspecified"))
      (node (ref "D3") (pin "1") (pinfunction "K_1") (pintype "unspecified"))
      (node (ref "U10") (pin "S") (pinfunction "S_S") (pintype "unspecified"))
    )
    (net (code "15") (name "EC_KEY_DET") (class "Default")
      (node (ref "D3") (pin "2") (pinfunction "A_2") (pintype "unspecified"))
      (node (ref "U1") (pin "39") (pinfunction "PB3_39") (pintype "input"))
    )
    (net (code "16") (name "GAUGE_INT") (class "Default")
      (node (ref "R24") (pin "1") (pinfunction "1_1") (pintype "input"))
      (node (ref "U1") (pin "22") (pinfunction "PB11_22") (pintype "input"))
      (node (ref "U13") (pin "A1") (pinfunction "GPOUT_A1") (pintype "unspecified"))
    )
    (net (code "17") (name "GND") (class "Default")
      (node (ref "C1") (pin "2") (pinfunction "2_2") (pintype "input"))
      (node (ref "C10") (pin "2") (pinfunction "2_2") (pintype "input"))
      (node (ref "C11") (pin "2") (pinfunction "2_2") (pintype "input"))
      (node (ref "C12") (pin "2") (pinfunction "2_2") (pintype "input"))
      (node (ref "C13") (pin "1") (pinfunction "1_1") (pintype "input"))
      (node (ref "C14") (pin "1") (pinfunction "1_1") (pintype "input"))
      (node (ref "C15") (pin "2") (pinfunction "2_2") (pintype "input"))
      (node (ref "C16") (pin "1") (pinfunction "1_1") (pintype "input"))
      (node (ref "C17") (pin "1") (pinfunction "1_1") (pintype "input"))
      (node (ref "C18") (pin "1") (pinfunction "1_1") (pintype "input"))
      (node (ref "C19") (pin "1") (pinfunction "1_1") (pintype "input"))
      (node (ref "C2") (pin "2") (pinfunction "2_2") (pintype "input"))
      (node (ref "C20") (pin "2") (pinfunction "2_2") (pintype "unspecified"))
      (node (ref "C21") (pin "1") (pinfunction "1_1") (pintype "unspecified"))
      (node (ref "C22") (pin "1") (pinfunction "1_1") (pintype "input"))
      (node (ref "C23") (pin "2") (pinfunction "2_2") (pintype "input"))
      (node (ref "C24") (pin "2") (pinfunction "2_2") (pintype "input"))
      (node (ref "C25") (pin "2") (pinfunction "2_2") (pintype "unspecified"))
      (node (ref "C26") (pin "2") (pinfunction "2_2") (pintype "unspecified"))
      (node (ref "C27") (pin "1") (pinfunction "1_1") (pintype "unspecified"))
      (node (ref "C28") (pin "2") (pinfunction "2_2") (pintype "input"))
      (node (ref "C29") (pin "1") (pinfunction "1_1") (pintype "unspecified"))
      (node (ref "C3") (pin "2") (pinfunction "2_2") (pintype "input"))
      (node (ref "C30") (pin "2") (pinfunction "2_2") (pintype "unspecified"))
      (node (ref "C31") (pin "2") (pinfunction "2_2") (pintype "input"))
      (node (ref "C32") (pin "1") (pinfunction "1_1") (pintype "unspecified"))
      (node (ref "C4") (pin "2") (pinfunction "2_2") (pintype "input"))
      (node (ref "C5") (pin "2") (pinfunction "2_2") (pintype "unspecified"))
      (node (ref "C6") (pin "2") (pinfunction "2_2") (pintype "unspecified"))
      (node (ref "C7") (pin "2") (pinfunction "2_2") (pintype "input"))
      (node (ref "C8") (pin "1") (pinfunction "1_1") (pintype "input"))
      (node (ref "C9") (pin "2") (pinfunction "2_2") (pintype "input"))
      (node (ref "CARD1") (pin "10") (pinfunction "GND_10") (pintype "unspecified"))
      (node (ref "CARD1") (pin "11") (pinfunction "GND_11") (pintype "unspecified"))
      (node (ref "CARD1") (pin "12") (pinfunction "GND_12") (pintype "unspecified"))
      (node (ref "CARD1") (pin "13") (pinfunction "GND_13") (pintype "unspecified"))
      (node (ref "CARD1") (pin "6") (pinfunction "VSS_6") (pintype "unspecified"))
      (node (ref "CN1") (pin "1") (pinfunction "1_1") (pintype "unspecified"))
      (node (ref "CN1") (pin "3") (pinfunction "3_3") (pintype "unspecified"))
      (node (ref "CN1") (pin "4") (pinfunction "4_4") (pintype "unspecified"))
      (node (ref "LCD1") (pin "1") (pinfunction "GND_1") (pintype "input"))
      (node (ref "LCD1") (pin "12") (pinfunction "GND_12") (pintype "input"))
      (node (ref "LCD1") (pin "5") (pinfunction "GND_5") (pintype "input"))
      (node (ref "LCD1") (pin "6") (pinfunction "GND_6") (pintype "input"))
      (node (ref "Q2") (pin "2") (pinfunction "S_2") (pintype "unspecified"))
      (node (ref "Q3") (pin "2") (pinfunction "S_2") (pintype "unspecified"))
      (node (ref "Q4") (pin "2") (pinfunction "S_2") (pintype "unspecified"))
      (node (ref "R1") (pin "2") (pinfunction "2_2") (pintype "input"))
      (node (ref "R15") (pin "2") (pinfunction "2_2") (pintype "input"))
      (node (ref "R16") (pin "2") (pinfunction "2_2") (pintype "input"))
      (node (ref "R17") (pin "1") (pinfunction "1_1") (pintype "input"))
      (node (ref "R18") (pin "1") (pinfunction "1_1") (pintype "input"))
      (node (ref "R20") (pin "1") (pinfunction "1_1") (pintype "input"))
      (node (ref "R25") (pin "2") (pinfunction "2_2") (pintype "input"))
      (node (ref "R5") (pin "2") (pinfunction "2_2") (pintype "input"))
      (node (ref "R6") (pin "1") (pinfunction "1_1") (pintype "input"))
      (node (ref "U1") (pin "23") (pinfunction "VSS_1_23") (pintype "input"))
      (node (ref "U1") (pin "35") (pinfunction "VSS_2_35") (pintype "input"))
      (node (ref "U1") (pin "44") (pinfunction "BOOT0_44") (pintype "input"))
      (node (ref "U1") (pin "47") (pinfunction "VSS_3_47") (pintype "input"))
      (node (ref "U1") (pin "49") (pinfunction "EP_49") (pintype "input"))
      (node (ref "U1") (pin "8") (pinfunction "VSSA_8") (pintype "input"))
      (node (ref "U10") (pin "1") (pinfunction "EH_1") (pintype "unspecified"))
      (node (ref "U10") (pin "2") (pinfunction "EH_2") (pintype "unspecified"))
      (node (ref "U10") (pin "3") (pinfunction "EH_3") (pintype "unspecified"))
      (node (ref "U10") (pin "4") (pinfunction "EH_4") (pintype "unspecified"))
      (node (ref "U10") (pin "5") (pinfunction "EH_5") (pintype "unspecified"))
      (node (ref "U10") (pin "6") (pinfunction "EH_6") (pintype "unspecified"))
      (node (ref "U10") (pin "C") (pinfunction "C_C") (pintype "unspecified"))
      (node (ref "U11") (pin "2") (pinfunction "VSS_2") (pintype "input"))
      (node (ref "U12") (pin "2") (pinfunction "GND_2") (pintype "unspecified"))
      (node (ref "U13") (pin "B2") (pinfunction "VSS_B2") (pintype "unspecified"))
      (node (ref "U14") (pin "1") (pinfunction "1_1") (pintype "unspecified"))
      (node (ref "U2") (pin "B1") (pinfunction "VSS_B1") (pintype "unspecified"))
      (node (ref "U3") (pin "1") (pinfunction "1_1") (pintype "unspecified"))
      (node (ref "U3") (pin "5") (pinfunction "5_5") (pintype "unspecified"))
      (node (ref "U3") (pin "6") (pinfunction "6_6") (pintype "unspecified"))
      (node (ref "U4") (pin "1") (pinfunction "1_1") (pintype "unspecified"))
      (node (ref "U4") (pin "5") (pinfunction "5_5") (pintype "unspecified"))
      (node (ref "U4") (pin "6") (pinfunction "6_6") (pintype "unspecified"))
      (node (ref "U5") (pin "1") (pinfunction "1_1") (pintype "unspecified"))
      (node (ref "U5") (pin "5") (pinfunction "5_5") (pintype "unspecified"))
      (node (ref "U5") (pin "6") (pinfunction "6_6") (pintype "unspecified"))
      (node (ref "U7") (pin "1") (pinfunction "1_1") (pintype "unspecified"))
      (node (ref "U7") (pin "A1") (pinfunction "A1_A1") (pintype "unspecified"))
      (node (ref "U7") (pin "A12") (pinfunction "A12_A12") (pintype "unspecified"))
      (node (ref "U8") (pin "1") (pinfunction "CLKIN_1") (pintype "unspecified"))
      (node (ref "U8") (pin "11") (pinfunction "FSYNC_11") (pintype "unspecified"))
      (node (ref "U8") (pin "18") (pinfunction "GND_18") (pintype "unspecified"))
      (node (ref "U8") (pin "25") (pinfunction "EP_25") (pintype "unspecified"))
      (node (ref "U9") (pin "3") (pinfunction "GND_3") (pintype "unspecified"))
    )
    (net (code "18") (name "GPS_RX") (class "Default")
      (node (ref "U1") (pin "12") (pinfunction "PA2_12") (pintype "input"))
      (node (ref "U3") (pin "2") (pinfunction "2_2") (pintype "unspecified"))
    )
    (net (code "19") (name "GPS_TX") (class "Default")
      (node (ref "U1") (pin "13") (pinfunction "PA3_13") (pintype "input"))
      (node (ref "U3") (pin "3") (pinfunction "3_3") (pintype "unspecified"))
    )
    (net (code "20") (name "IMU_INT1") (class "Default")
      (node (ref "U1") (pin "21") (pinfunction "PB10_21") (pintype "input"))
      (node (ref "U8") (pin "12") (pinfunction "INT_12") (pintype "unspecified"))
    )
    (net (code "21") (name "MCU_RX") (class "Default")
      (node (ref "R10") (pin "1") (pinfunction "1_1") (pintype "input"))
      (node (ref "U1") (pin "31") (pinfunction "PA10_31") (pintype "input"))
    )
    (net (code "22") (name "MCU_SCL") (class "Default")
      (node (ref "R21") (pin "2") (pinfunction "2_2") (pintype "input"))
      (node (ref "R8") (pin "2") (pinfunction "2_2") (pintype "input"))
      (node (ref "U1") (pin "42") (pinfunction "PB6_42") (pintype "input"))
      (node (ref "U13") (pin "A3") (pinfunction "SCL_A3") (pintype "unspecified"))
      (node (ref "U4") (pin "2") (pinfunction "2_2") (pintype "unspecified"))
      (node (ref "U8") (pin "23") (pinfunction "SCL_23") (pintype "unspecified"))
    )
    (net (code "23") (name "MCU_SDA") (class "Default")
      (node (ref "R11") (pin "2") (pinfunction "2_2") (pintype "input"))
      (node (ref "R22") (pin "2") (pinfunction "2_2") (pintype "input"))
      (node (ref "U1") (pin "43") (pinfunction "PB7_43") (pintype "input"))
      (node (ref "U13") (pin "A2") (pinfunction "SDA_A2") (pintype "unspecified"))
      (node (ref "U4") (pin "3") (pinfunction "3_3") (pintype "unspecified"))
      (node (ref "U8") (pin "24") (pinfunction "SDA_24") (pintype "unspecified"))
    )
    (net (code "24") (name "MCU_TX") (class "Default")
      (node (ref "R9") (pin "1") (pinfunction "1_1") (pintype "input"))
      (node (ref "U1") (pin "30") (pinfunction "PA9_30") (pintype "input"))
    )
    (net (code "25") (name "Net-(D2-A)") (class "Default")
      (node (ref "D2") (pin "2") (pinfunction "A_2") (pintype "unspecified"))
      (node (ref "Q1") (pin "1") (pinfunction "G_1") (pintype "unspecified"))
      (node (ref "Q2") (pin "3") (pinfunction "D_3") (pintype "unspecified"))
      (node (ref "R4") (pin "2") (pinfunction "2_2") (pintype "input"))
    )
    (net (code "26") (name "Net-(D4-K)") (class "Default")
      (node (ref "D4") (pin "1") (pinfunction "K_1") (pintype "unspecified"))
      (node (ref "D5") (pin "1") (pinfunction "K_1") (pintype "unspecified"))
      (node (ref "Q2") (pin "1") (pinfunction "G_1") (pintype "unspecified"))
      (node (ref "R6") (pin "2") (pinfunction "2_2") (pintype "input"))
    )
    (net (code "27") (name "Net-(LED1--)") (class "Default")
      (node (ref "LED1") (pin "2") (pinfunction "-_2") (pintype "unspecified"))
      (node (ref "R2") (pin "1") (pinfunction "1_1") (pintype "input"))
    )
    (net (code "28") (name "Net-(Q3-D)") (class "Default")
      (node (ref "Q3") (pin "3") (pinfunction "D_3") (pintype "unspecified"))
      (node (ref "R12") (pin "2") (pinfunction "2_2") (pintype "input"))
    )
    (net (code "29") (name "Net-(Q4-D)") (class "Default")
      (node (ref "BUZZER1") (pin "2") (pinfunction "2_2") (pintype "input"))
      (node (ref "Q4") (pin "3") (pinfunction "D_3") (pintype "unspecified"))
    )
    (net (code "30") (name "Net-(R17-Pad2)") (class "Default")
      (node (ref "R17") (pin "2") (pinfunction "2_2") (pintype "input"))
      (node (ref "U7") (pin "A5") (pinfunction "A5_A5") (pintype "unspecified"))
    )
    (net (code "31") (name "Net-(R18-Pad2)") (class "Default")
      (node (ref "R18") (pin "2") (pinfunction "2_2") (pintype "input"))
      (node (ref "U7") (pin "B5") (pinfunction "B5_B5") (pintype "unspecified"))
    )
    (net (code "32") (name "Net-(U2-C1)") (class "Default")
      (node (ref "C20") (pin "1") (pinfunction "1_1") (pintype "unspecified"))
      (node (ref "U2") (pin "A3") (pinfunction "C1_A3") (pintype "unspecified"))
    )
    (net (code "33") (name "Net-(U8-AD0)") (class "Default")
      (node (ref "R20") (pin "2") (pinfunction "2_2") (pintype "input"))
      (node (ref "U8") (pin "9") (pinfunction "AD0_9") (pintype "unspecified"))
    )
    (net (code "34") (name "Net-(U8-CPOUT)") (class "Default")
      (node (ref "C28") (pin "1") (pinfunction "1_1") (pintype "input"))
      (node (ref "U8") (pin "20") (pinfunction "CPOUT_20") (pintype "unspecified"))
    )
    (net (code "35") (name "Net-(U8-REGOUT)") (class "Default")
      (node (ref "C30") (pin "1") (pinfunction "1_1") (pintype "unspecified"))
      (node (ref "U8") (pin "10") (pinfunction "REGOUT_10") (pintype "unspecified"))
    )
    (net (code "36") (name "Net-(U9-RST#)") (class "Default")
      (node (ref "R19") (pin "1") (pinfunction "1_1") (pintype "input"))
      (node (ref "U9") (pin "9") (pinfunction "RST#_9") (pintype "unspecified"))
    )
    (net (code "37") (name "Net-(U9-RXD)") (class "Default")
      (node (ref "R9") (pin "2") (pinfunction "2_2") (pintype "input"))
      (node (ref "U9") (pin "25") (pinfunction "RXD_25") (pintype "unspecified"))
    )
    (net (code "38") (name "Net-(U9-TXD)") (class "Default")
      (node (ref "R10") (pin "2") (pinfunction "2_2") (pintype "input"))
      (node (ref "U9") (pin "26") (pinfunction "TXD_26") (pintype "unspecified"))
    )
    (net (code "39") (name "Net-(U11-PROG)") (class "Default")
      (node (ref "R1") (pin "1") (pinfunction "1_1") (pintype "input"))
      (node (ref "U11") (pin "5") (pinfunction "PROG_5") (pintype "input"))
    )
    (net (code "40") (name "Net-(U13-BIN)") (class "Default")
      (node (ref "R25") (pin "1") (pinfunction "1_1") (pintype "input"))
      (node (ref "U13") (pin "B1") (pinfunction "BIN_B1") (pintype "unspecified"))
    )
    (net (code "41") (name "OSC32_IN") (class "Default")
      (node (ref "C14") (pin "2") (pinfunction "2_2") (pintype "input"))
      (node (ref "U1") (pin "3") (pinfunction "PC14/OSC32_IN_3") (pintype "input"))
      (node (ref "Y1") (pin "1") (pinfunction "1_1") (pintype "unspecified"))
    )
    (net (code "42") (name "OSC32_OUT") (class "Default")
      (node (ref "C15") (pin "1") (pinfunction "1_1") (pintype "input"))
      (node (ref "U1") (pin "4") (pinfunction "PC15/OSC32_OUT_4") (pintype "input"))
      (node (ref "Y1") (pin "2") (pinfunction "2_2") (pintype "unspecified"))
    )
    (net (code "43") (name "PWR_EN") (class "Default")
      (node (ref "D5") (pin "2") (pinfunction "A_2") (pintype "unspecified"))
      (node (ref "U1") (pin "33") (pinfunction "PA12_33") (pintype "input"))
    )
    (net (code "44") (name "RST") (class "Default")
      (node (ref "C13") (pin "2") (pinfunction "2_2") (pintype "input"))
      (node (ref "R7") (pin "2") (pinfunction "2_2") (pintype "input"))
      (node (ref "U1") (pin "7") (pinfunction "NRST_7") (pintype "input"))
      (node (ref "U14") (pin "2") (pinfunction "2_2") (pintype "unspecified"))
    )
    (net (code "45") (name "SCR_BLK") (class "Default")
      (node (ref "Q3") (pin "1") (pinfunction "G_1") (pintype "unspecified"))
      (node (ref "R15") (pin "1") (pinfunction "1_1") (pintype "input"))
      (node (ref "U1") (pin "19") (pinfunction "PB1_19") (pintype "input"))
    )
    (net (code "46") (name "SCR_CS") (class "Default")
      (node (ref "LCD1") (pin "8") (pinfunction "CS_8") (pintype "input"))
      (node (ref "U1") (pin "18") (pinfunction "PB0_18") (pintype "input"))
    )
    (net (code "47") (name "SCR_DC") (class "Default")
      (node (ref "LCD1") (pin "7") (pinfunction "D/C_7") (pintype "input"))
      (node (ref "U1") (pin "14") (pinfunction "PA4_14") (pintype "input"))
    )
    (net (code "48") (name "SCR_LEDK") (class "Default")
      (node (ref "LCD1") (pin "2") (pinfunction "LEDK_2") (pintype "input"))
      (node (ref "R12") (pin "1") (pinfunction "1_1") (pintype "input"))
    )
    (net (code "49") (name "SCR_RES") (class "Default")
      (node (ref "LCD1") (pin "11") (pinfunction "RESET_11") (pintype "input"))
      (node (ref "U1") (pin "16") (pinfunction "PA6_16") (pintype "input"))
    )
    (net (code "50") (name "SCR_SCL") (class "Default")
      (node (ref "LCD1") (pin "9") (pinfunction "SCL_9") (pintype "input"))
      (node (ref "U1") (pin "15") (pinfunction "PA5_15") (pintype "input"))
    )
    (net (code "51") (name "SCR_SDA") (class "Default")
      (node (ref "LCD1") (pin "10") (pinfunction "SDA_10") (pintype "input"))
      (node (ref "U1") (pin "17") (pinfunction "PA7_17") (pintype "input"))
    )
    (net (code "52") (name "SD_CD") (class "Default")
      (node (ref "CARD1") (pin "9") (pinfunction "CD_9") (pintype "unspecified"))
      (node (ref "U1") (pin "29") (pinfunction "PA8_29") (pintype "input"))
    )
    (net (code "53") (name "SD_CS") (class "Default")
      (node (ref "CARD1") (pin "2") (pinfunction "CD/DATA3_2") (pintype "unspecified"))
      (node (ref "U1") (pin "25") (pinfunction "PB12_25") (pintype "input"))
    )
    (net (code "54") (name "SD_MISO") (class "Default")
      (node (ref "CARD1") (pin "7") (pinfunction "DAT0_7") (pintype "unspecified"))
      (node (ref "U1") (pin "27") (pinfunction "PB14_27") (pintype "input"))
    )
    (net (code "55") (name "SD_MOSI") (class "Default")
      (node (ref "CARD1") (pin "3") (pinfunction "CMD_3") (pintype "unspecified"))
      (node (ref "U1") (pin "28") (pinfunction "PB15_28") (pintype "input"))
    )
    (net (code "56") (name "SD_SCK") (class "Default")
      (node (ref "CARD1") (pin "5") (pinfunction "CLK_5") (pintype "unspecified"))
      (node (ref "U1") (pin "26") (pinfunction "PB13_26") (pintype "input"))
    )
    (net (code "57") (name "SWCLK") (class "Default")
      (node (ref "U1") (pin "37") (pinfunction "PA14_37") (pintype "input"))
      (node (ref "U5") (pin "3") (pinfunction "3_3") (pintype "unspecified"))
    )
    (net (code "58") (name "SWDIO") (class "Default")
      (node (ref "U1") (pin "34") (pinfunction "PA13_34") (pintype "input"))
      (node (ref "U5") (pin "2") (pinfunction "2_2") (pintype "unspecified"))
    )
    (net (code "59") (name "USB_VCC") (class "Default")
      (node (ref "C25") (pin "1") (pinfunction "1_1") (pintype "unspecified"))
      (node (ref "C26") (pin "1") (pinfunction "1_1") (pintype "unspecified"))
      (node (ref "C3") (pin "1") (pinfunction "1_1") (pintype "input"))
      (node (ref "D4") (pin "2") (pinfunction "A_2") (pintype "unspecified"))
      (node (ref "LED1") (pin "1") (pinfunction "+_1") (pintype "unspecified"))
      (node (ref "R26") (pin "1") (pinfunction "1_1") (pintype "input"))
      (node (ref "U11") (pin "4") (pinfunction "VDD_4") (pintype "input"))
      (node (ref "U7") (pin "A4") (pinfunction "A4_A4") (pintype "unspecified"))
      (node (ref "U7") (pin "A9") (pinfunction "A9_A9") (pintype "unspecified"))
      (node (ref "U9") (pin "7") (pinfunction "REGIN_7") (pintype "unspecified"))
      (node (ref "U9") (pin "8") (pinfunction "VBUS_8") (pintype "unspecified"))
    )
    (net (code "60") (name "V33_CP2102") (class "Default")
      (node (ref "C17") (pin "2") (pinfunction "2_2") (pintype "input"))
      (node (ref "C27") (pin "2") (pinfunction "2_2") (pintype "unspecified"))
      (node (ref "R19") (pin "2") (pinfunction "2_2") (pintype "input"))
      (node (ref "U9") (pin "6") (pinfunction "VDD_6") (pintype "unspecified"))
    )
    (net (code "61") (name "VBAT") (class "Default")
      (node (ref "C8") (pin "2") (pinfunction "2_2") (pintype "input"))
      (node (ref "D6") (pin "1") (pinfunction "K_1") (pintype "unspecified"))
      (node (ref "U1") (pin "1") (pinfunction "VBAT_1") (pintype "input"))
    )
    (net (code "62") (name "VDD_GAUGE") (class "Default")
      (node (ref "C31") (pin "1") (pinfunction "1_1") (pintype "input"))
      (node (ref "U13") (pin "B3") (pinfunction "VDD_B3") (pintype "unspecified"))
    )
    (net (code "63") (name "unconnected-(BUZZER1-Pad3)") (class "Default")
      (node (ref "BUZZER1") (pin "3") (pinfunction "3_3") (pintype "input+no_connect"))
    )
    (net (code "64") (name "unconnected-(CARD1-DAT1-Pad8)") (class "Default")
      (node (ref "CARD1") (pin "8") (pinfunction "DAT1_8") (pintype "unspecified+no_connect"))
    )
    (net (code "65") (name "unconnected-(CARD1-DATA2-Pad1)") (class "Default")
      (node (ref "CARD1") (pin "1") (pinfunction "DATA2_1") (pintype "unspecified+no_connect"))
    )
    (net (code "66") (name "unconnected-(U1-PA15-Pad38)") (class "Default")
      (node (ref "U1") (pin "38") (pinfunction "PA15_38") (pintype "input+no_connect"))
    )
    (net (code "67") (name "unconnected-(U1-PB2-Pad20)") (class "Default")
      (node (ref "U1") (pin "20") (pinfunction "PB2_20") (pintype "input+no_connect"))
    )
    (net (code "68") (name "unconnected-(U1-PB8-Pad45)") (class "Default")
      (node (ref "U1") (pin "45") (pinfunction "PB8_45") (pintype "input+no_connect"))
    )
    (net (code "69") (name "unconnected-(U1-PB9-Pad46)") (class "Default")
      (node (ref "U1") (pin "46") (pinfunction "PB9_46") (pintype "input+no_connect"))
    )
    (net (code "70") (name "unconnected-(U1-PC13{slash}TAMPER-RTC-Pad2)") (class "Default")
      (node (ref "U1") (pin "2") (pinfunction "PC13/TAMPER-RTC_2") (pintype "input+no_connect"))
    )
    (net (code "71") (name "unconnected-(U1-PD0{slash}OSC_IN-Pad5)") (class "Default")
      (node (ref "U1") (pin "5") (pinfunction "PD0/OSC_IN_5") (pintype "input+no_connect"))
    )
    (net (code "72") (name "unconnected-(U1-PD1{slash}OSC_OUT-Pad6)") (class "Default")
      (node (ref "U1") (pin "6") (pinfunction "PD1/OSC_OUT_6") (pintype "input+no_connect"))
    )
    (net (code "73") (name "unconnected-(U2-NC-PadA2)") (class "Default")
      (node (ref "U2") (pin "A2") (pinfunction "NC_A2") (pintype "unspecified+no_connect"))
    )
    (net (code "74") (name "unconnected-(U2-NC-PadC1)") (class "Default")
      (node (ref "U2") (pin "C1") (pinfunction "NC_C1") (pintype "unspecified+no_connect"))
    )
    (net (code "75") (name "unconnected-(U2-NC-PadC2)") (class "Default")
      (node (ref "U2") (pin "C2") (pinfunction "NC_C2") (pintype "unspecified+no_connect"))
    )
    (net (code "76") (name "unconnected-(U7-PadA8)") (class "Default")
      (node (ref "U7") (pin "A8") (pinfunction "A8_A8") (pintype "unspecified+no_connect"))
    )
    (net (code "77") (name "unconnected-(U7-PadB8)") (class "Default")
      (node (ref "U7") (pin "B8") (pinfunction "B8_B8") (pintype "unspecified+no_connect"))
    )
    (net (code "78") (name "unconnected-(U8-NC-Pad2)") (class "Default")
      (node (ref "U8") (pin "2") (pinfunction "NC_2") (pintype "unspecified+no_connect"))
    )
    (net (code "79") (name "unconnected-(U8-NC-Pad3)") (class "Default")
      (node (ref "U8") (pin "3") (pinfunction "NC_3") (pintype "unspecified+no_connect"))
    )
    (net (code "80") (name "unconnected-(U8-NC-Pad4)") (class "Default")
      (node (ref "U8") (pin "4") (pinfunction "NC_4") (pintype "unspecified+no_connect"))
    )
    (net (code "81") (name "unconnected-(U8-NC-Pad5)") (class "Default")
      (node (ref "U8") (pin "5") (pinfunction "NC_5") (pintype "unspecified+no_connect"))
    )
    (net (code "82") (name "unconnected-(U8-NC-Pad14)") (class "Default")
      (node (ref "U8") (pin "14") (pinfunction "NC_14") (pintype "unspecified+no_connect"))
    )
    (net (code "83") (name "unconnected-(U8-NC-Pad15)") (class "Default")
      (node (ref "U8") (pin "15") (pinfunction "NC_15") (pintype "unspecified+no_connect"))
    )
    (net (code "84") (name "unconnected-(U8-NC-Pad16)") (class "Default")
      (node (ref "U8") (pin "16") (pinfunction "NC_16") (pintype "unspecified+no_connect"))
    )
    (net (code "85") (name "unconnected-(U8-NC-Pad17)") (class "Default")
      (node (ref "U8") (pin "17") (pinfunction "NC_17") (pintype "unspecified+no_connect"))
    )
    (net (code "86") (name "unconnected-(U8-RESV-Pad19)") (class "Default")
      (node (ref "U8") (pin "19") (pinfunction "RESV_19") (pintype "unspecified+no_connect"))
    )
    (net (code "87") (name "unconnected-(U8-RESV-Pad21)") (class "Default")
      (node (ref "U8") (pin "21") (pinfunction "RESV_21") (pintype "unspecified+no_connect"))
    )
    (net (code "88") (name "unconnected-(U8-RESV-Pad22)") (class "Default")
      (node (ref "U8") (pin "22") (pinfunction "RESV_22") (pintype "unspecified+no_connect"))
    )
    (net (code "89") (name "unconnected-(U9-CTS-Pad23)") (class "Default")
      (node (ref "U9") (pin "23") (pinfunction "CTS_23") (pintype "unspecified+no_connect"))
    )
    (net (code "90") (name "unconnected-(U9-DCD-Pad1)") (class "Default")
      (node (ref "U9") (pin "1") (pinfunction "DCD_1") (pintype "unspecified+no_connect"))
    )
    (net (code "91") (name "unconnected-(U9-DSR-Pad27)") (class "Default")
      (node (ref "U9") (pin "27") (pinfunction "DSR_27") (pintype "unspecified+no_connect"))
    )
    (net (code "92") (name "unconnected-(U9-DTR-Pad28)") (class "Default")
      (node (ref "U9") (pin "28") (pinfunction "DTR_28") (pintype "unspecified+no_connect"))
    )
    (net (code "93") (name "unconnected-(U9-EP-Pad29)") (class "Default")
      (node (ref "U9") (pin "29") (pinfunction "EP_29") (pintype "unspecified+no_connect"))
    )
    (net (code "94") (name "unconnected-(U9-NC-Pad10)") (class "Default")
      (node (ref "U9") (pin "10") (pinfunction "NC_10") (pintype "unspecified+no_connect"))
    )
    (net (code "95") (name "unconnected-(U9-NC-Pad13)") (class "Default")
      (node (ref "U9") (pin "13") (pinfunction "NC_13") (pintype "unspecified+no_connect"))
    )
    (net (code "96") (name "unconnected-(U9-NC-Pad14)") (class "Default")
      (node (ref "U9") (pin "14") (pinfunction "NC_14") (pintype "unspecified+no_connect"))
    )
    (net (code "97") (name "unconnected-(U9-NC-Pad15)") (class "Default")
      (node (ref "U9") (pin "15") (pinfunction "NC_15") (pintype "unspecified+no_connect"))
    )
    (net (code "98") (name "unconnected-(U9-NC-Pad16)") (class "Default")
      (node (ref "U9") (pin "16") (pinfunction "NC_16") (pintype "unspecified+no_connect"))
    )
    (net (code "99") (name "unconnected-(U9-NC-Pad17)") (class "Default")
      (node (ref "U9") (pin "17") (pinfunction "NC_17") (pintype "unspecified+no_connect"))
    )
    (net (code "100") (name "unconnected-(U9-NC-Pad18)") (class "Default")
      (node (ref "U9") (pin "18") (pinfunction "NC_18") (pintype "unspecified+no_connect"))
    )
    (net (code "101") (name "unconnected-(U9-NC-Pad19)") (class "Default")
      (node (ref "U9") (pin "19") (pinfunction "NC_19") (pintype "unspecified+no_connect"))
    )
    (net (code "102") (name "unconnected-(U9-NC-Pad20)") (class "Default")
      (node (ref "U9") (pin "20") (pinfunction "NC_20") (pintype "unspecified+no_connect"))
    )
    (net (code "103") (name "unconnected-(U9-NC-Pad21)") (class "Default")
      (node (ref "U9") (pin "21") (pinfunction "NC_21") (pintype "unspecified+no_connect"))
    )
    (net (code "104") (name "unconnected-(U9-NC-Pad22)") (class "Default")
      (node (ref "U9") (pin "22") (pinfunction "NC_22") (pintype "unspecified+no_connect"))
    )
    (net (code "105") (name "unconnected-(U9-RI-Pad2)") (class "Default")
      (node (ref "U9") (pin "2") (pinfunction "RI_2") (pintype "unspecified+no_connect"))
    )
    (net (code "106") (name "unconnected-(U9-RTS-Pad24)") (class "Default")
      (node (ref "U9") (pin "24") (pinfunction "RTS_24") (pintype "unspecified+no_connect"))
    )
    (net (code "107") (name "unconnected-(U9-SUSPEND#-Pad11)") (class "Default")
      (node (ref "U9") (pin "11") (pinfunction "SUSPEND#_11") (pintype "unspecified+no_connect"))
    )
    (net (code "108") (name "unconnected-(U9-SUSPEND-Pad12)") (class "Default")
      (node (ref "U9") (pin "12") (pinfunction "SUSPEND_12") (pintype "unspecified+no_connect"))
    )
    (net (code "109") (name "unconnected-(U12-N{slash}C-Pad4)") (class "Default")
      (node (ref "U12") (pin "4") (pinfunction "N/C_4") (pintype "unspecified+no_connect"))
    )
  )
)
